# split36_right.net
KiCad netlist of a schematic drawn in EasyEDA Pro
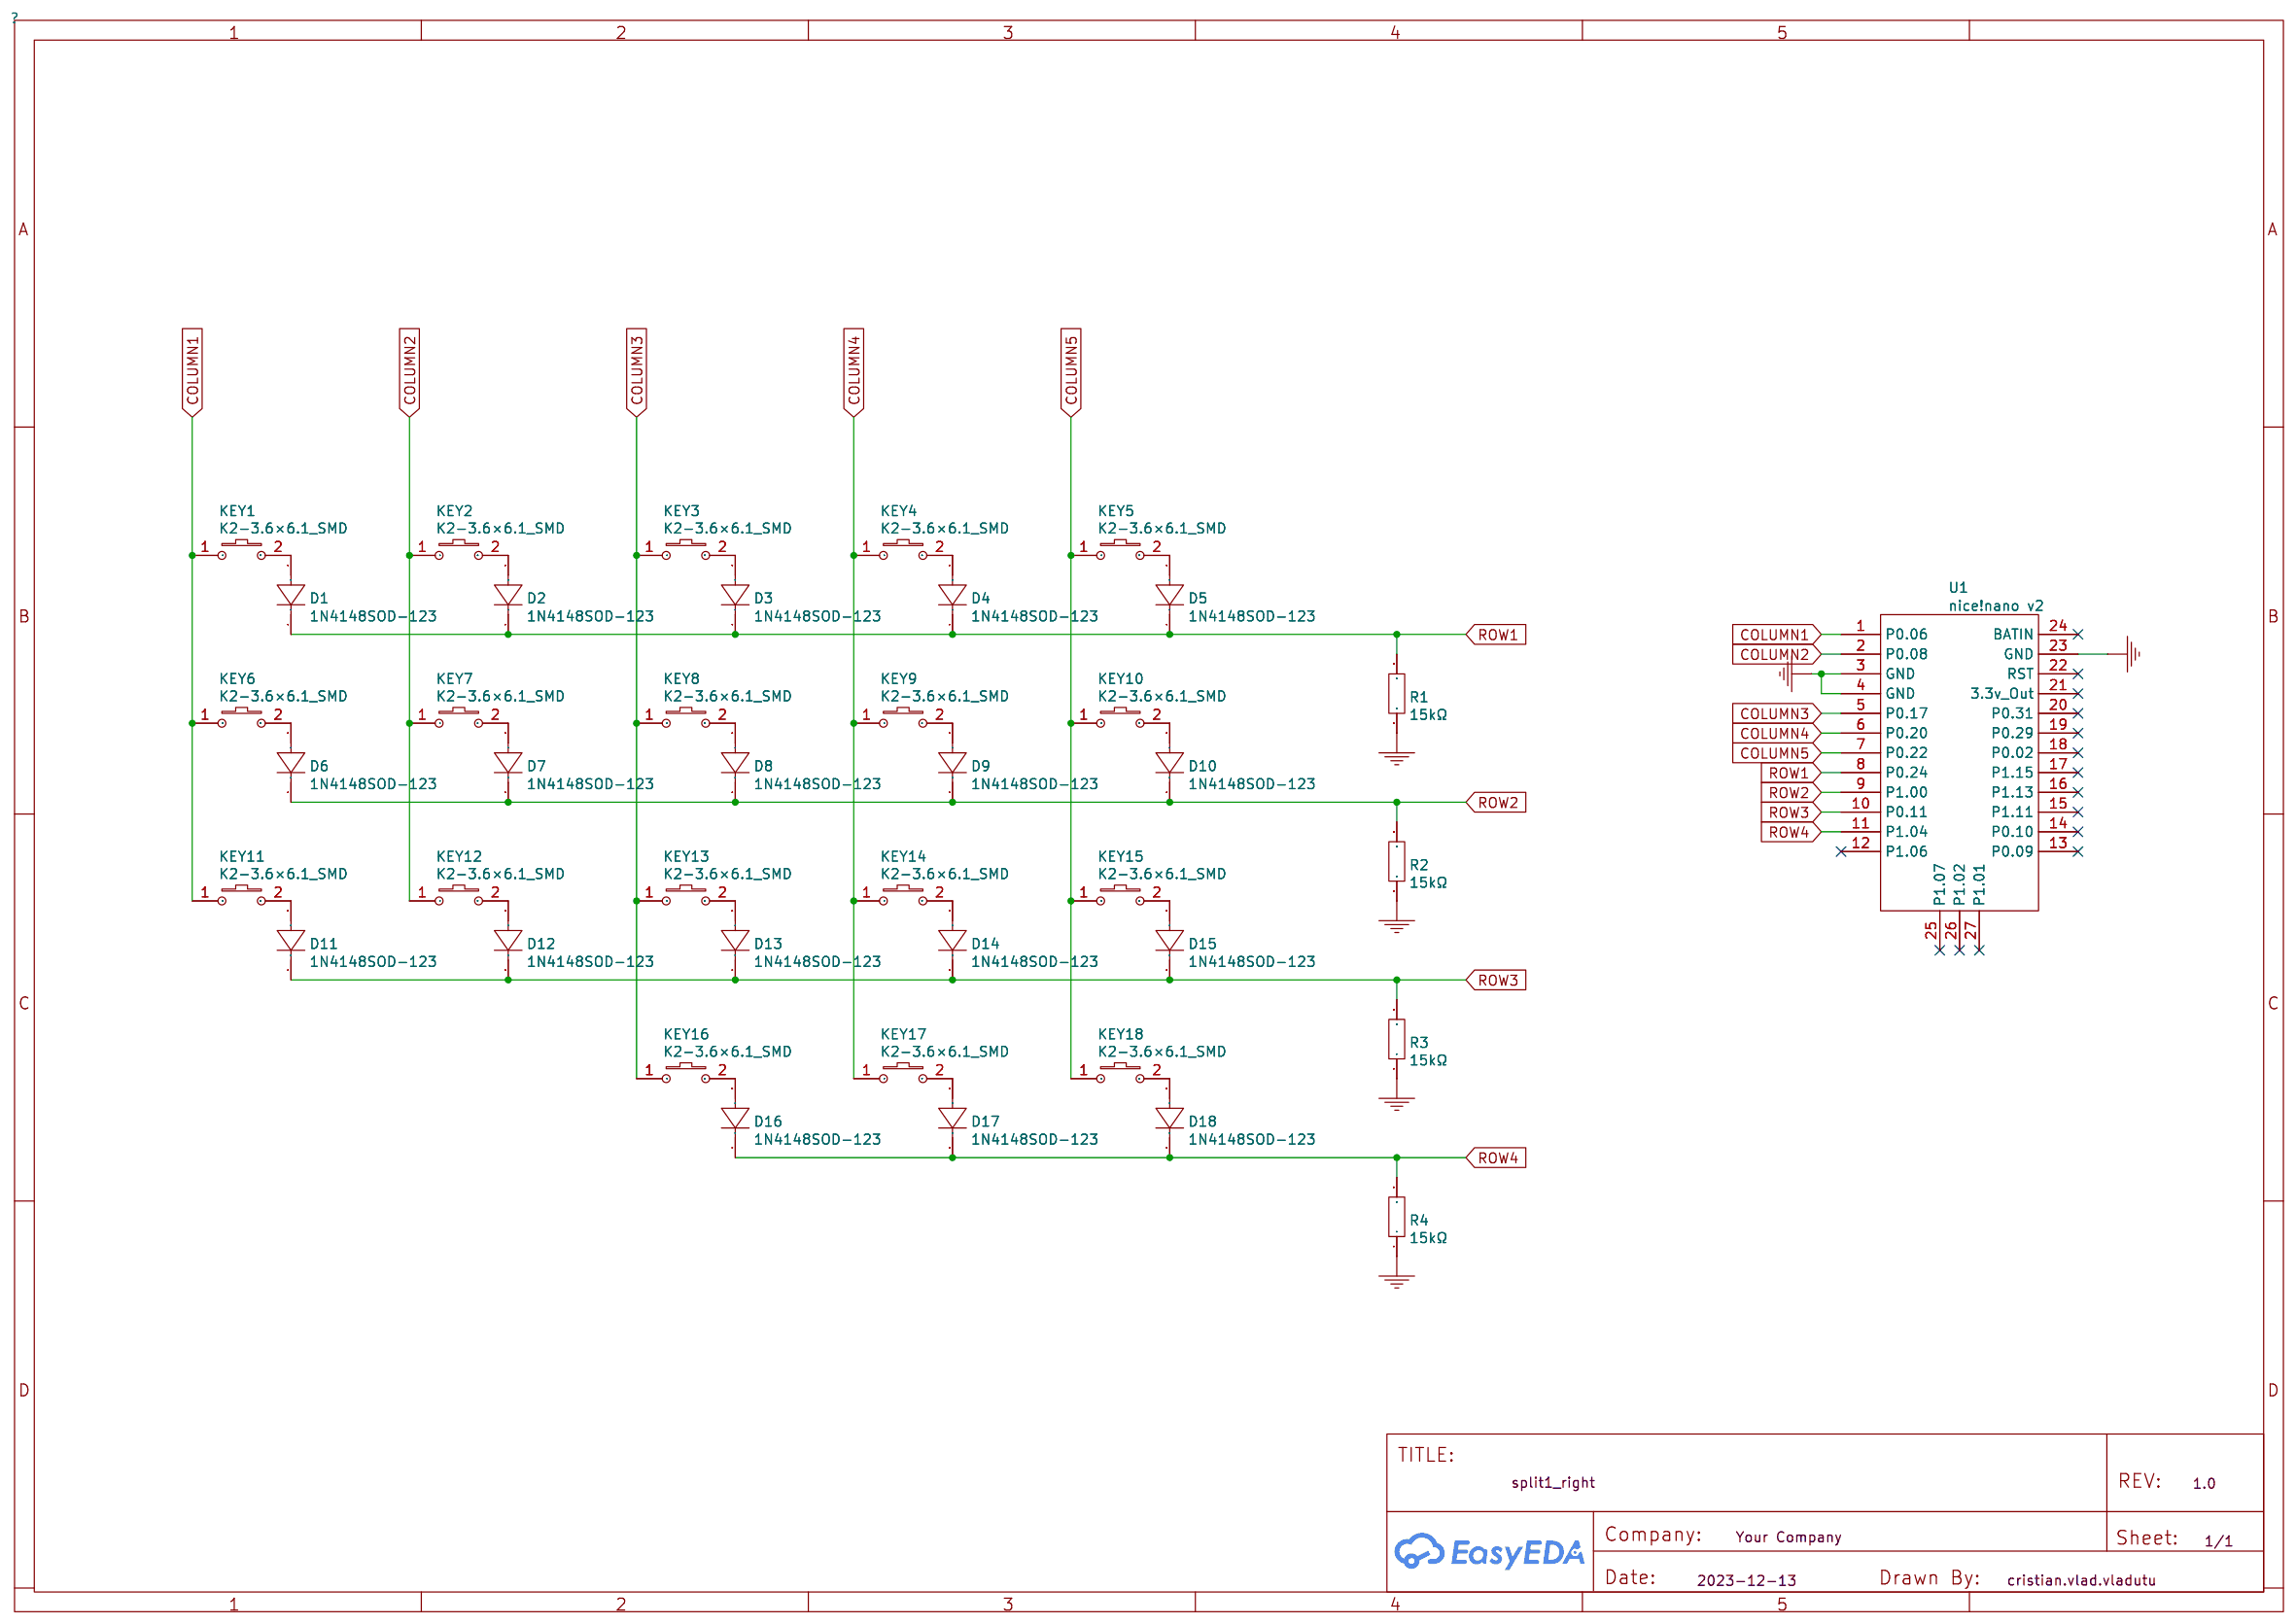
[diagram p0: schematic sheet]

(export (version "E")
  (design (tool "Eeschema 10.0.6"))
  (components
    (comp (ref "D1")
      (value "1N4148SOD-123")
      (footprint "easyedapro:SOD-123_L2.6-W1.6-LS3.5-RD")
      (fields (field (name "Manufacturer") "JKSEMI(金开盛)"))
      (libsource (lib "easyedapro") (part "1N4148SOD-123"))
    )
    (comp (ref "D2")
      (value "1N4148SOD-123")
      (footprint "easyedapro:SOD-123_L2.6-W1.6-LS3.5-RD")
      (fields (field (name "Manufacturer") "JKSEMI(金开盛)"))
      (libsource (lib "easyedapro") (part "1N4148SOD-123"))
    )
    (comp (ref "D3")
      (value "1N4148SOD-123")
      (footprint "easyedapro:SOD-123_L2.6-W1.6-LS3.5-RD")
      (fields (field (name "Manufacturer") "JKSEMI(金开盛)"))
      (libsource (lib "easyedapro") (part "1N4148SOD-123"))
    )
    (comp (ref "D4")
      (value "1N4148SOD-123")
      (footprint "easyedapro:SOD-123_L2.6-W1.6-LS3.5-RD")
      (fields (field (name "Manufacturer") "JKSEMI(金开盛)"))
      (libsource (lib "easyedapro") (part "1N4148SOD-123"))
    )
    (comp (ref "D5")
      (value "1N4148SOD-123")
      (footprint "easyedapro:SOD-123_L2.6-W1.6-LS3.5-RD")
      (fields (field (name "Manufacturer") "JKSEMI(金开盛)"))
      (libsource (lib "easyedapro") (part "1N4148SOD-123"))
    )
    (comp (ref "D6")
      (value "1N4148SOD-123")
      (footprint "easyedapro:SOD-123_L2.6-W1.6-LS3.5-RD")
      (fields (field (name "Manufacturer") "JKSEMI(金开盛)"))
      (libsource (lib "easyedapro") (part "1N4148SOD-123"))
    )
    (comp (ref "D7")
      (value "1N4148SOD-123")
      (footprint "easyedapro:SOD-123_L2.6-W1.6-LS3.5-RD")
      (fields (field (name "Manufacturer") "JKSEMI(金开盛)"))
      (libsource (lib "easyedapro") (part "1N4148SOD-123"))
    )
    (comp (ref "D8")
      (value "1N4148SOD-123")
      (footprint "easyedapro:SOD-123_L2.6-W1.6-LS3.5-RD")
      (fields (field (name "Manufacturer") "JKSEMI(金开盛)"))
      (libsource (lib "easyedapro") (part "1N4148SOD-123"))
    )
    (comp (ref "D9")
      (value "1N4148SOD-123")
      (footprint "easyedapro:SOD-123_L2.6-W1.6-LS3.5-RD")
      (fields (field (name "Manufacturer") "JKSEMI(金开盛)"))
      (libsource (lib "easyedapro") (part "1N4148SOD-123"))
    )
    (comp (ref "D10")
      (value "1N4148SOD-123")
      (footprint "easyedapro:SOD-123_L2.6-W1.6-LS3.5-RD")
      (fields (field (name "Manufacturer") "JKSEMI(金开盛)"))
      (libsource (lib "easyedapro") (part "1N4148SOD-123"))
    )
    (comp (ref "D11")
      (value "1N4148SOD-123")
      (footprint "easyedapro:SOD-123_L2.6-W1.6-LS3.5-RD")
      (fields (field (name "Manufacturer") "JKSEMI(金开盛)"))
      (libsource (lib "easyedapro") (part "1N4148SOD-123"))
    )
    (comp (ref "D12")
      (value "1N4148SOD-123")
      (footprint "easyedapro:SOD-123_L2.6-W1.6-LS3.5-RD")
      (fields (field (name "Manufacturer") "JKSEMI(金开盛)"))
      (libsource (lib "easyedapro") (part "1N4148SOD-123"))
    )
    (comp (ref "D13")
      (value "1N4148SOD-123")
      (footprint "easyedapro:SOD-123_L2.6-W1.6-LS3.5-RD")
      (fields (field (name "Manufacturer") "JKSEMI(金开盛)"))
      (libsource (lib "easyedapro") (part "1N4148SOD-123"))
    )
    (comp (ref "D14")
      (value "1N4148SOD-123")
      (footprint "easyedapro:SOD-123_L2.6-W1.6-LS3.5-RD")
      (fields (field (name "Manufacturer") "JKSEMI(金开盛)"))
      (libsource (lib "easyedapro") (part "1N4148SOD-123"))
    )
    (comp (ref "D15")
      (value "1N4148SOD-123")
      (footprint "easyedapro:SOD-123_L2.6-W1.6-LS3.5-RD")
      (fields (field (name "Manufacturer") "JKSEMI(金开盛)"))
      (libsource (lib "easyedapro") (part "1N4148SOD-123"))
    )
    (comp (ref "D16")
      (value "1N4148SOD-123")
      (footprint "easyedapro:SOD-123_L2.6-W1.6-LS3.5-RD")
      (fields (field (name "Manufacturer") "JKSEMI(金开盛)"))
      (libsource (lib "easyedapro") (part "1N4148SOD-123"))
    )
    (comp (ref "D17")
      (value "1N4148SOD-123")
      (footprint "easyedapro:SOD-123_L2.6-W1.6-LS3.5-RD")
      (fields (field (name "Manufacturer") "JKSEMI(金开盛)"))
      (libsource (lib "easyedapro") (part "1N4148SOD-123"))
    )
    (comp (ref "D18")
      (value "1N4148SOD-123")
      (footprint "easyedapro:SOD-123_L2.6-W1.6-LS3.5-RD")
      (fields (field (name "Manufacturer") "JKSEMI(金开盛)"))
      (libsource (lib "easyedapro") (part "1N4148SOD-123"))
    )
    (comp (ref "KEY1")
      (value "K2-3.6×6.1_SMD")
      (footprint "easyedapro:GATERON LOW PROFILE SWITCH HOTSWAP LED")
      (fields (field (name "Manufacturer Part") "K2-1107ST-A4SW-06"))
      (libsource (lib "easyedapro") (part "K2-3.6×6.1_SMD"))
    )
    (comp (ref "KEY2")
      (value "K2-3.6×6.1_SMD")
      (footprint "easyedapro:GATERON LOW PROFILE SWITCH HOTSWAP LED")
      (fields (field (name "Manufacturer Part") "K2-1107ST-A4SW-06"))
      (libsource (lib "easyedapro") (part "K2-3.6×6.1_SMD"))
    )
    (comp (ref "KEY3")
      (value "K2-3.6×6.1_SMD")
      (footprint "easyedapro:GATERON LOW PROFILE SWITCH HOTSWAP LED")
      (fields (field (name "Manufacturer Part") "K2-1107ST-A4SW-06"))
      (libsource (lib "easyedapro") (part "K2-3.6×6.1_SMD"))
    )
    (comp (ref "KEY4")
      (value "K2-3.6×6.1_SMD")
      (footprint "easyedapro:GATERON LOW PROFILE SWITCH HOTSWAP LED")
      (fields (field (name "Manufacturer Part") "K2-1107ST-A4SW-06"))
      (libsource (lib "easyedapro") (part "K2-3.6×6.1_SMD"))
    )
    (comp (ref "KEY5")
      (value "K2-3.6×6.1_SMD")
      (footprint "easyedapro:GATERON LOW PROFILE SWITCH HOTSWAP LED")
      (fields (field (name "Manufacturer Part") "K2-1107ST-A4SW-06"))
      (libsource (lib "easyedapro") (part "K2-3.6×6.1_SMD"))
    )
    (comp (ref "KEY6")
      (value "K2-3.6×6.1_SMD")
      (footprint "easyedapro:GATERON LOW PROFILE SWITCH HOTSWAP LED")
      (fields (field (name "Manufacturer Part") "K2-1107ST-A4SW-06"))
      (libsource (lib "easyedapro") (part "K2-3.6×6.1_SMD"))
    )
    (comp (ref "KEY7")
      (value "K2-3.6×6.1_SMD")
      (footprint "easyedapro:GATERON LOW PROFILE SWITCH HOTSWAP LED")
      (fields (field (name "Manufacturer Part") "K2-1107ST-A4SW-06"))
      (libsource (lib "easyedapro") (part "K2-3.6×6.1_SMD"))
    )
    (comp (ref "KEY8")
      (value "K2-3.6×6.1_SMD")
      (footprint "easyedapro:GATERON LOW PROFILE SWITCH HOTSWAP LED")
      (fields (field (name "Manufacturer Part") "K2-1107ST-A4SW-06"))
      (libsource (lib "easyedapro") (part "K2-3.6×6.1_SMD"))
    )
    (comp (ref "KEY9")
      (value "K2-3.6×6.1_SMD")
      (footprint "easyedapro:GATERON LOW PROFILE SWITCH HOTSWAP LED")
      (fields (field (name "Manufacturer Part") "K2-1107ST-A4SW-06"))
      (libsource (lib "easyedapro") (part "K2-3.6×6.1_SMD"))
    )
    (comp (ref "KEY10")
      (value "K2-3.6×6.1_SMD")
      (footprint "easyedapro:GATERON LOW PROFILE SWITCH HOTSWAP LED")
      (fields (field (name "Manufacturer Part") "K2-1107ST-A4SW-06"))
      (libsource (lib "easyedapro") (part "K2-3.6×6.1_SMD"))
    )
    (comp (ref "KEY11")
      (value "K2-3.6×6.1_SMD")
      (footprint "easyedapro:GATERON LOW PROFILE SWITCH HOTSWAP LED")
      (fields (field (name "Manufacturer Part") "K2-1107ST-A4SW-06"))
      (libsource (lib "easyedapro") (part "K2-3.6×6.1_SMD"))
    )
    (comp (ref "KEY12")
      (value "K2-3.6×6.1_SMD")
      (footprint "easyedapro:GATERON LOW PROFILE SWITCH HOTSWAP LED")
      (fields (field (name "Manufacturer Part") "K2-1107ST-A4SW-06"))
      (libsource (lib "easyedapro") (part "K2-3.6×6.1_SMD"))
    )
    (comp (ref "KEY13")
      (value "K2-3.6×6.1_SMD")
      (footprint "easyedapro:GATERON LOW PROFILE SWITCH HOTSWAP LED")
      (fields (field (name "Manufacturer Part") "K2-1107ST-A4SW-06"))
      (libsource (lib "easyedapro") (part "K2-3.6×6.1_SMD"))
    )
    (comp (ref "KEY14")
      (value "K2-3.6×6.1_SMD")
      (footprint "easyedapro:GATERON LOW PROFILE SWITCH HOTSWAP LED")
      (fields (field (name "Manufacturer Part") "K2-1107ST-A4SW-06"))
      (libsource (lib "easyedapro") (part "K2-3.6×6.1_SMD"))
    )
    (comp (ref "KEY15")
      (value "K2-3.6×6.1_SMD")
      (footprint "easyedapro:GATERON LOW PROFILE SWITCH HOTSWAP LED")
      (fields (field (name "Manufacturer Part") "K2-1107ST-A4SW-06"))
      (libsource (lib "easyedapro") (part "K2-3.6×6.1_SMD"))
    )
    (comp (ref "KEY16")
      (value "K2-3.6×6.1_SMD")
      (footprint "easyedapro:GATERON LOW PROFILE SWITCH HOTSWAP LED")
      (fields (field (name "Manufacturer Part") "K2-1107ST-A4SW-06"))
      (libsource (lib "easyedapro") (part "K2-3.6×6.1_SMD"))
    )
    (comp (ref "KEY17")
      (value "K2-3.6×6.1_SMD")
      (footprint "easyedapro:GATERON LOW PROFILE SWITCH HOTSWAP LED")
      (fields (field (name "Manufacturer Part") "K2-1107ST-A4SW-06"))
      (libsource (lib "easyedapro") (part "K2-3.6×6.1_SMD"))
    )
    (comp (ref "KEY18")
      (value "K2-3.6×6.1_SMD")
      (footprint "easyedapro:GATERON LOW PROFILE SWITCH HOTSWAP LED")
      (fields (field (name "Manufacturer Part") "K2-1107ST-A4SW-06"))
      (libsource (lib "easyedapro") (part "K2-3.6×6.1_SMD"))
    )
    (comp (ref "R1")
      (value "15kΩ")
      (footprint "easyedapro:R0402")
      (fields (field (name "Manufacturer Part") "RMC040215K5%N") (field (name "Manufacturer") "Tyohm(幸亚电阻)"))
      (libsource (lib "easyedapro") (part "15kΩ"))
    )
    (comp (ref "R2")
      (value "15kΩ")
      (footprint "easyedapro:R0402")
      (fields (field (name "Manufacturer Part") "RMC040215K5%N") (field (name "Manufacturer") "Tyohm(幸亚电阻)"))
      (libsource (lib "easyedapro") (part "15kΩ"))
    )
    (comp (ref "R3")
      (value "15kΩ")
      (footprint "easyedapro:R0402")
      (fields (field (name "Manufacturer Part") "RMC040215K5%N") (field (name "Manufacturer") "Tyohm(幸亚电阻)"))
      (libsource (lib "easyedapro") (part "15kΩ"))
    )
    (comp (ref "R4")
      (value "15kΩ")
      (footprint "easyedapro:R0402")
      (fields (field (name "Manufacturer Part") "RMC040215K5%N") (field (name "Manufacturer") "Tyohm(幸亚电阻)"))
      (libsource (lib "easyedapro") (part "15kΩ"))
    )
    (comp (ref "U1")
      (value "nice!nano v2")
      (footprint "easyedapro:NICE!NANO V2")
      (fields (field (name "Manufacturer") "nice!"))
      (libsource (lib "easyedapro") (part "nice!nano v2"))
    )
  )
  (nets
    (net (code "1") (name "COLUMN1") (class "Default")
      (node (ref "KEY1") (pin "1") (pinfunction "1_1") (pintype "unspecified"))
      (node (ref "KEY11") (pin "1") (pinfunction "1_1") (pintype "unspecified"))
      (node (ref "KEY6") (pin "1") (pinfunction "1_1") (pintype "unspecified"))
      (node (ref "U1") (pin "1") (pinfunction "P0.06_1") (pintype "input"))
    )
    (net (code "2") (name "COLUMN2") (class "Default")
      (node (ref "KEY12") (pin "1") (pinfunction "1_1") (pintype "unspecified"))
      (node (ref "KEY2") (pin "1") (pinfunction "1_1") (pintype "unspecified"))
      (node (ref "KEY7") (pin "1") (pinfunction "1_1") (pintype "unspecified"))
      (node (ref "U1") (pin "2") (pinfunction "P0.08_2") (pintype "input"))
    )
    (net (code "3") (name "COLUMN3") (class "Default")
      (node (ref "KEY13") (pin "1") (pinfunction "1_1") (pintype "unspecified"))
      (node (ref "KEY16") (pin "1") (pinfunction "1_1") (pintype "unspecified"))
      (node (ref "KEY3") (pin "1") (pinfunction "1_1") (pintype "unspecified"))
      (node (ref "KEY8") (pin "1") (pinfunction "1_1") (pintype "unspecified"))
      (node (ref "U1") (pin "5") (pinfunction "P0.17_5") (pintype "unspecified"))
    )
    (net (code "4") (name "COLUMN4") (class "Default")
      (node (ref "KEY14") (pin "1") (pinfunction "1_1") (pintype "unspecified"))
      (node (ref "KEY17") (pin "1") (pinfunction "1_1") (pintype "unspecified"))
      (node (ref "KEY4") (pin "1") (pinfunction "1_1") (pintype "unspecified"))
      (node (ref "KEY9") (pin "1") (pinfunction "1_1") (pintype "unspecified"))
      (node (ref "U1") (pin "6") (pinfunction "P0.20_6") (pintype "unspecified"))
    )
    (net (code "5") (name "COLUMN5") (class "Default")
      (node (ref "KEY10") (pin "1") (pinfunction "1_1") (pintype "unspecified"))
      (node (ref "KEY15") (pin "1") (pinfunction "1_1") (pintype "unspecified"))
      (node (ref "KEY18") (pin "1") (pinfunction "1_1") (pintype "unspecified"))
      (node (ref "KEY5") (pin "1") (pinfunction "1_1") (pintype "unspecified"))
      (node (ref "U1") (pin "7") (pinfunction "P0.22_7") (pintype "unspecified"))
    )
    (net (code "6") (name "GND") (class "Default")
      (node (ref "R1") (pin "1") (pinfunction "1_1") (pintype "unspecified"))
      (node (ref "R2") (pin "1") (pinfunction "1_1") (pintype "unspecified"))
      (node (ref "R3") (pin "1") (pinfunction "1_1") (pintype "unspecified"))
      (node (ref "R4") (pin "1") (pinfunction "1_1") (pintype "unspecified"))
      (node (ref "U1") (pin "23") (pinfunction "GND_23") (pintype "bidirectional"))
      (node (ref "U1") (pin "3") (pinfunction "GND_3") (pintype "unspecified"))
      (node (ref "U1") (pin "4") (pinfunction "GND_4") (pintype "unspecified"))
    )
    (net (code "7") (name "Net-(D1-A)") (class "Default")
      (node (ref "D1") (pin "2") (pinfunction "A_2") (pintype "unspecified"))
      (node (ref "KEY1") (pin "2") (pinfunction "2_2") (pintype "unspecified"))
    )
    (net (code "8") (name "Net-(D2-A)") (class "Default")
      (node (ref "D2") (pin "2") (pinfunction "A_2") (pintype "unspecified"))
      (node (ref "KEY2") (pin "2") (pinfunction "2_2") (pintype "unspecified"))
    )
    (net (code "9") (name "Net-(D3-A)") (class "Default")
      (node (ref "D3") (pin "2") (pinfunction "A_2") (pintype "unspecified"))
      (node (ref "KEY3") (pin "2") (pinfunction "2_2") (pintype "unspecified"))
    )
    (net (code "10") (name "Net-(D4-A)") (class "Default")
      (node (ref "D4") (pin "2") (pinfunction "A_2") (pintype "unspecified"))
      (node (ref "KEY4") (pin "2") (pinfunction "2_2") (pintype "unspecified"))
    )
    (net (code "11") (name "Net-(D5-A)") (class "Default")
      (node (ref "D5") (pin "2") (pinfunction "A_2") (pintype "unspecified"))
      (node (ref "KEY5") (pin "2") (pinfunction "2_2") (pintype "unspecified"))
    )
    (net (code "12") (name "Net-(D6-A)") (class "Default")
      (node (ref "D6") (pin "2") (pinfunction "A_2") (pintype "unspecified"))
      (node (ref "KEY6") (pin "2") (pinfunction "2_2") (pintype "unspecified"))
    )
    (net (code "13") (name "Net-(D7-A)") (class "Default")
      (node (ref "D7") (pin "2") (pinfunction "A_2") (pintype "unspecified"))
      (node (ref "KEY7") (pin "2") (pinfunction "2_2") (pintype "unspecified"))
    )
    (net (code "14") (name "Net-(D8-A)") (class "Default")
      (node (ref "D8") (pin "2") (pinfunction "A_2") (pintype "unspecified"))
      (node (ref "KEY8") (pin "2") (pinfunction "2_2") (pintype "unspecified"))
    )
    (net (code "15") (name "Net-(D9-A)") (class "Default")
      (node (ref "D9") (pin "2") (pinfunction "A_2") (pintype "unspecified"))
      (node (ref "KEY9") (pin "2") (pinfunction "2_2") (pintype "unspecified"))
    )
    (net (code "16") (name "Net-(D10-A)") (class "Default")
      (node (ref "D10") (pin "2") (pinfunction "A_2") (pintype "unspecified"))
      (node (ref "KEY10") (pin "2") (pinfunction "2_2") (pintype "unspecified"))
    )
    (net (code "17") (name "Net-(D11-A)") (class "Default")
      (node (ref "D11") (pin "2") (pinfunction "A_2") (pintype "unspecified"))
      (node (ref "KEY11") (pin "2") (pinfunction "2_2") (pintype "unspecified"))
    )
    (net (code "18") (name "Net-(D12-A)") (class "Default")
      (node (ref "D12") (pin "2") (pinfunction "A_2") (pintype "unspecified"))
      (node (ref "KEY12") (pin "2") (pinfunction "2_2") (pintype "unspecified"))
    )
    (net (code "19") (name "Net-(D13-A)") (class "Default")
      (node (ref "D13") (pin "2") (pinfunction "A_2") (pintype "unspecified"))
      (node (ref "KEY13") (pin "2") (pinfunction "2_2") (pintype "unspecified"))
    )
    (net (code "20") (name "Net-(D14-A)") (class "Default")
      (node (ref "D14") (pin "2") (pinfunction "A_2") (pintype "unspecified"))
      (node (ref "KEY14") (pin "2") (pinfunction "2_2") (pintype "unspecified"))
    )
    (net (code "21") (name "Net-(D15-A)") (class "Default")
      (node (ref "D15") (pin "2") (pinfunction "A_2") (pintype "unspecified"))
      (node (ref "KEY15") (pin "2") (pinfunction "2_2") (pintype "unspecified"))
    )
    (net (code "22") (name "Net-(D16-A)") (class "Default")
      (node (ref "D16") (pin "2") (pinfunction "A_2") (pintype "unspecified"))
      (node (ref "KEY16") (pin "2") (pinfunction "2_2") (pintype "unspecified"))
    )
    (net (code "23") (name "Net-(D17-A)") (class "Default")
      (node (ref "D17") (pin "2") (pinfunction "A_2") (pintype "unspecified"))
      (node (ref "KEY17") (pin "2") (pinfunction "2_2") (pintype "unspecified"))
    )
    (net (code "24") (name "Net-(D18-A)") (class "Default")
      (node (ref "D18") (pin "2") (pinfunction "A_2") (pintype "unspecified"))
      (node (ref "KEY18") (pin "2") (pinfunction "2_2") (pintype "unspecified"))
    )
    (net (code "25") (name "ROW1") (class "Default")
      (node (ref "D1") (pin "1") (pinfunction "K_1") (pintype "unspecified"))
      (node (ref "D2") (pin "1") (pinfunction "K_1") (pintype "unspecified"))
      (node (ref "D3") (pin "1") (pinfunction "K_1") (pintype "unspecified"))
      (node (ref "D4") (pin "1") (pinfunction "K_1") (pintype "unspecified"))
      (node (ref "D5") (pin "1") (pinfunction "K_1") (pintype "unspecified"))
      (node (ref "R1") (pin "2") (pinfunction "2_2") (pintype "unspecified"))
      (node (ref "U1") (pin "8") (pinfunction "P0.24_8") (pintype "unspecified"))
    )
    (net (code "26") (name "ROW2") (class "Default")
      (node (ref "D10") (pin "1") (pinfunction "K_1") (pintype "unspecified"))
      (node (ref "D6") (pin "1") (pinfunction "K_1") (pintype "unspecified"))
      (node (ref "D7") (pin "1") (pinfunction "K_1") (pintype "unspecified"))
      (node (ref "D8") (pin "1") (pinfunction "K_1") (pintype "unspecified"))
      (node (ref "D9") (pin "1") (pinfunction "K_1") (pintype "unspecified"))
      (node (ref "R2") (pin "2") (pinfunction "2_2") (pintype "unspecified"))
      (node (ref "U1") (pin "9") (pinfunction "P1.00_9") (pintype "unspecified"))
    )
    (net (code "27") (name "ROW3") (class "Default")
      (node (ref "D11") (pin "1") (pinfunction "K_1") (pintype "unspecified"))
      (node (ref "D12") (pin "1") (pinfunction "K_1") (pintype "unspecified"))
      (node (ref "D13") (pin "1") (pinfunction "K_1") (pintype "unspecified"))
      (node (ref "D14") (pin "1") (pinfunction "K_1") (pintype "unspecified"))
      (node (ref "D15") (pin "1") (pinfunction "K_1") (pintype "unspecified"))
      (node (ref "R3") (pin "2") (pinfunction "2_2") (pintype "unspecified"))
      (node (ref "U1") (pin "10") (pinfunction "P0.11_10") (pintype "unspecified"))
    )
    (net (code "28") (name "ROW4") (class "Default")
      (node (ref "D16") (pin "1") (pinfunction "K_1") (pintype "unspecified"))
      (node (ref "D17") (pin "1") (pinfunction "K_1") (pintype "unspecified"))
      (node (ref "D18") (pin "1") (pinfunction "K_1") (pintype "unspecified"))
      (node (ref "R4") (pin "2") (pinfunction "2_2") (pintype "unspecified"))
      (node (ref "U1") (pin "11") (pinfunction "P1.04_11") (pintype "unspecified"))
    )
    (net (code "29") (name "unconnected-(U1-3.3v_Out-Pad21)") (class "Default")
      (node (ref "U1") (pin "21") (pinfunction "3.3v_Out_21") (pintype "bidirectional+no_connect"))
    )
    (net (code "30") (name "unconnected-(U1-BATIN-Pad24)") (class "Default")
      (node (ref "U1") (pin "24") (pinfunction "BATIN_24") (pintype "bidirectional+no_connect"))
    )
    (net (code "31") (name "unconnected-(U1-P0.02-Pad18)") (class "Default")
      (node (ref "U1") (pin "18") (pinfunction "P0.02_18") (pintype "bidirectional+no_connect"))
    )
    (net (code "32") (name "unconnected-(U1-P0.09-Pad13)") (class "Default")
      (node (ref "U1") (pin "13") (pinfunction "P0.09_13") (pintype "bidirectional+no_connect"))
    )
    (net (code "33") (name "unconnected-(U1-P0.10-Pad14)") (class "Default")
      (node (ref "U1") (pin "14") (pinfunction "P0.10_14") (pintype "bidirectional+no_connect"))
    )
    (net (code "34") (name "unconnected-(U1-P0.29-Pad19)") (class "Default")
      (node (ref "U1") (pin "19") (pinfunction "P0.29_19") (pintype "bidirectional+no_connect"))
    )
    (net (code "35") (name "unconnected-(U1-P0.31-Pad20)") (class "Default")
      (node (ref "U1") (pin "20") (pinfunction "P0.31_20") (pintype "bidirectional+no_connect"))
    )
    (net (code "36") (name "unconnected-(U1-P1.01-Pad27)") (class "Default")
      (node (ref "U1") (pin "27") (pinfunction "P1.01_27") (pintype "unspecified+no_connect"))
    )
    (net (code "37") (name "unconnected-(U1-P1.02-Pad26)") (class "Default")
      (node (ref "U1") (pin "26") (pinfunction "P1.02_26") (pintype "unspecified+no_connect"))
    )
    (net (code "38") (name "unconnected-(U1-P1.06-Pad12)") (class "Default")
      (node (ref "U1") (pin "12") (pinfunction "P1.06_12") (pintype "unspecified+no_connect"))
    )
    (net (code "39") (name "unconnected-(U1-P1.07-Pad25)") (class "Default")
      (node (ref "U1") (pin "25") (pinfunction "P1.07_25") (pintype "unspecified+no_connect"))
    )
    (net (code "40") (name "unconnected-(U1-P1.11-Pad15)") (class "Default")
      (node (ref "U1") (pin "15") (pinfunction "P1.11_15") (pintype "bidirectional+no_connect"))
    )
    (net (code "41") (name "unconnected-(U1-P1.13-Pad16)") (class "Default")
      (node (ref "U1") (pin "16") (pinfunction "P1.13_16") (pintype "bidirectional+no_connect"))
    )
    (net (code "42") (name "unconnected-(U1-P1.15-Pad17)") (class "Default")
      (node (ref "U1") (pin "17") (pinfunction "P1.15_17") (pintype "bidirectional+no_connect"))
    )
    (net (code "43") (name "unconnected-(U1-RST-Pad22)") (class "Default")
      (node (ref "U1") (pin "22") (pinfunction "RST_22") (pintype "bidirectional+no_connect"))
    )
  )
)
